# Sensor_tile2.net
KiCad netlist of a schematic drawn in EAGLE
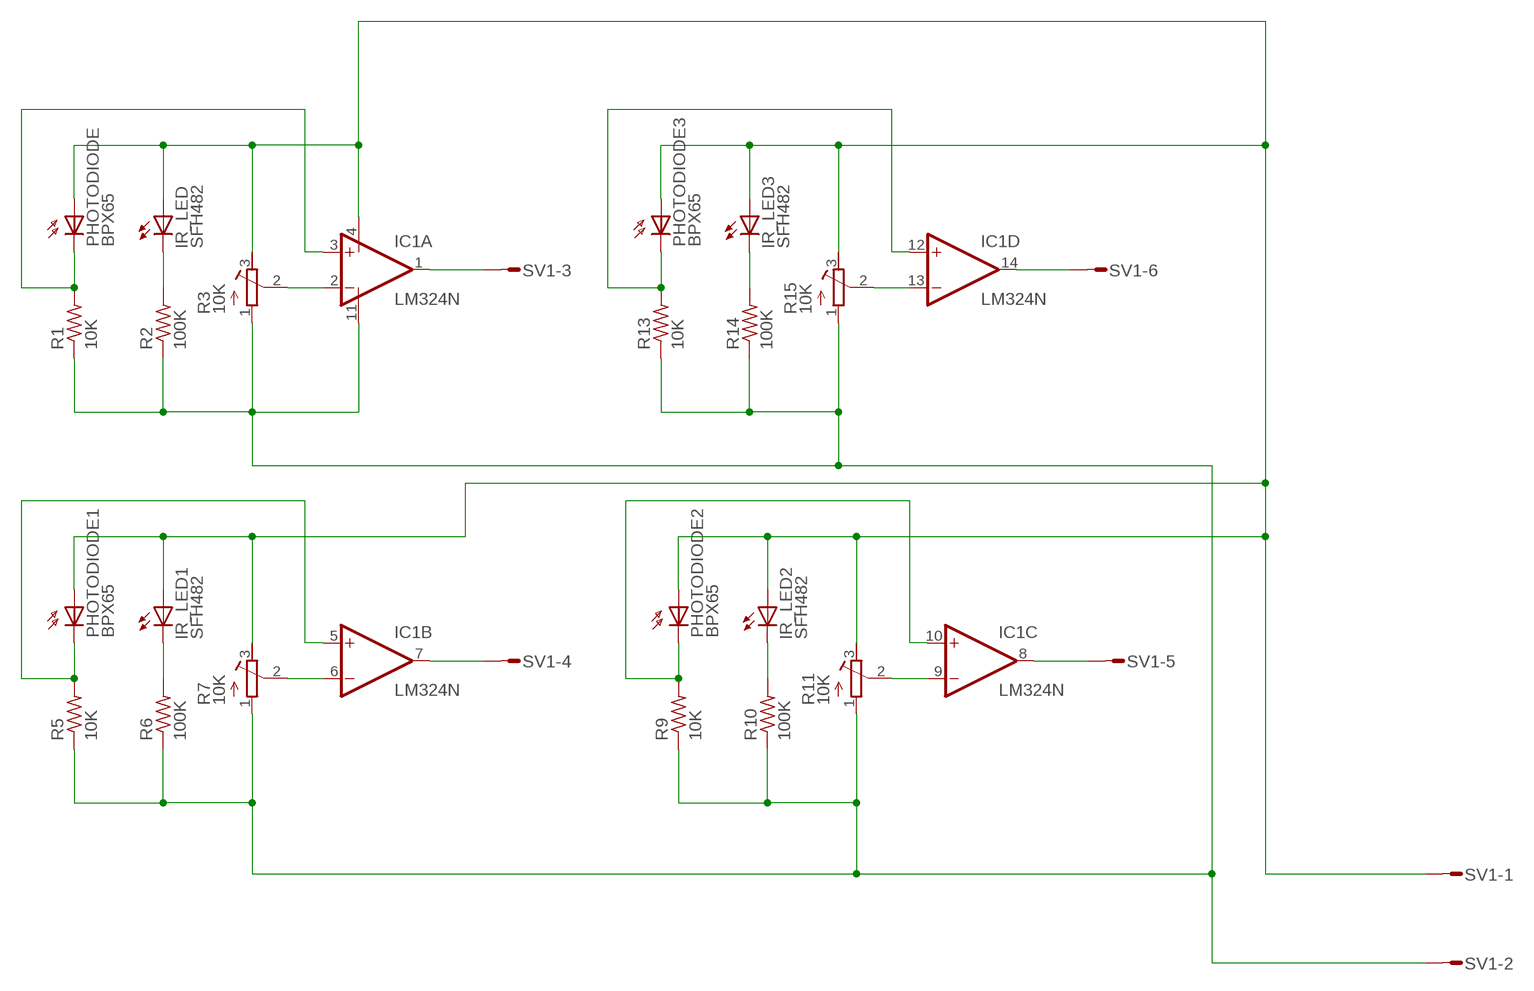
[diagram p0: schematic, sheet 1]

(export (version "E")
  (design (tool "Eeschema 10.0.6"))
  (components
    (comp (ref "IC1")
      (value "LM324N")
      (footprint "eagle-import:DIL14")
      (libsource (lib "eagle-import") (part "LM324N"))
    )
    (comp (ref "IR_LED")
      (value "SFH482")
      (footprint "eagle-import:SFH482")
      (libsource (lib "eagle-import") (part "SFH482"))
    )
    (comp (ref "IR_LED1")
      (value "SFH482")
      (footprint "eagle-import:SFH482")
      (libsource (lib "eagle-import") (part "SFH482"))
    )
    (comp (ref "IR_LED2")
      (value "SFH482")
      (footprint "eagle-import:SFH482")
      (libsource (lib "eagle-import") (part "SFH482"))
    )
    (comp (ref "IR_LED3")
      (value "SFH482")
      (footprint "eagle-import:SFH482")
      (libsource (lib "eagle-import") (part "SFH482"))
    )
    (comp (ref "PHOTODIODE")
      (value "BPX65")
      (footprint "eagle-import:BPX65")
      (fields (field (name "MPN") "BPX65."))
      (libsource (lib "eagle-import") (part "BPX65"))
    )
    (comp (ref "PHOTODIODE1")
      (value "BPX65")
      (footprint "eagle-import:BPX65")
      (fields (field (name "MPN") "BPX65."))
      (libsource (lib "eagle-import") (part "BPX65"))
    )
    (comp (ref "PHOTODIODE2")
      (value "BPX65")
      (footprint "eagle-import:BPX65")
      (fields (field (name "MPN") "BPX65."))
      (libsource (lib "eagle-import") (part "BPX65"))
    )
    (comp (ref "PHOTODIODE3")
      (value "BPX65")
      (footprint "eagle-import:BPX65")
      (fields (field (name "MPN") "BPX65."))
      (libsource (lib "eagle-import") (part "BPX65"))
    )
    (comp (ref "R1")
      (value "10K")
      (footprint "eagle-import:0204_7")
      (libsource (lib "eagle-import") (part "R-US_0204/7"))
    )
    (comp (ref "R2")
      (value "100K")
      (footprint "eagle-import:0204_7")
      (libsource (lib "eagle-import") (part "R-US_0204/7"))
    )
    (comp (ref "R3")
      (value "10K")
      (footprint "eagle-import:RTRIM4G_J")
      (libsource (lib "eagle-import") (part "R-TRIMM4G/J"))
    )
    (comp (ref "R5")
      (value "10K")
      (footprint "eagle-import:0204_7")
      (libsource (lib "eagle-import") (part "R-US_0204/7"))
    )
    (comp (ref "R6")
      (value "100K")
      (footprint "eagle-import:0204_7")
      (libsource (lib "eagle-import") (part "R-US_0204/7"))
    )
    (comp (ref "R7")
      (value "10K")
      (footprint "eagle-import:RTRIM4G_J")
      (libsource (lib "eagle-import") (part "R-TRIMM4G/J"))
    )
    (comp (ref "R9")
      (value "10K")
      (footprint "eagle-import:0204_7")
      (libsource (lib "eagle-import") (part "R-US_0204/7"))
    )
    (comp (ref "R10")
      (value "100K")
      (footprint "eagle-import:0204_7")
      (libsource (lib "eagle-import") (part "R-US_0204/7"))
    )
    (comp (ref "R11")
      (value "10K")
      (footprint "eagle-import:RTRIM4G_J")
      (libsource (lib "eagle-import") (part "R-TRIMM4G/J"))
    )
    (comp (ref "R13")
      (value "10K")
      (footprint "eagle-import:0204_7")
      (libsource (lib "eagle-import") (part "R-US_0204/7"))
    )
    (comp (ref "R14")
      (value "100K")
      (footprint "eagle-import:0204_7")
      (libsource (lib "eagle-import") (part "R-US_0204/7"))
    )
    (comp (ref "R15")
      (value "10K")
      (footprint "eagle-import:RTRIM4G_J")
      (libsource (lib "eagle-import") (part "R-TRIMM4G/J"))
    )
    (comp (ref "SV1")
      (value "L06P")
      (footprint "eagle-import:L06P")
      (libsource (lib "eagle-import") (part "L06P"))
    )
  )
  (nets
    (net (code "1") (name "Net-(IC1A-+IN)") (class "Default")
      (node (ref "IC1") (pin "3") (pinfunction "+IN_3") (pintype "input"))
      (node (ref "PHOTODIODE") (pin "K") (pinfunction "C_K") (pintype "passive"))
      (node (ref "R1") (pin "2") (pinfunction "2_2") (pintype "passive"))
    )
    (net (code "2") (name "Net-(IC1A--IN)") (class "Default")
      (node (ref "IC1") (pin "2") (pinfunction "-IN_2") (pintype "input"))
      (node (ref "R3") (pin "2") (pinfunction "S_2") (pintype "passive"))
    )
    (net (code "3") (name "Net-(IC1A-OUT)") (class "Default")
      (node (ref "IC1") (pin "1") (pinfunction "OUT_1") (pintype "output"))
      (node (ref "SV1") (pin "3") (pinfunction "S_3") (pintype "passive"))
    )
    (net (code "4") (name "Net-(IC1B-+IN)") (class "Default")
      (node (ref "IC1") (pin "5") (pinfunction "+IN_5") (pintype "input"))
      (node (ref "PHOTODIODE1") (pin "K") (pinfunction "C_K") (pintype "passive"))
      (node (ref "R5") (pin "2") (pinfunction "2_2") (pintype "passive"))
    )
    (net (code "5") (name "Net-(IC1B--IN)") (class "Default")
      (node (ref "IC1") (pin "6") (pinfunction "-IN_6") (pintype "input"))
      (node (ref "R7") (pin "2") (pinfunction "S_2") (pintype "passive"))
    )
    (net (code "6") (name "Net-(IC1B-OUT)") (class "Default")
      (node (ref "IC1") (pin "7") (pinfunction "OUT_7") (pintype "output"))
      (node (ref "SV1") (pin "4") (pinfunction "S_4") (pintype "passive"))
    )
    (net (code "7") (name "Net-(IC1C-+IN)") (class "Default")
      (node (ref "IC1") (pin "10") (pinfunction "+IN_10") (pintype "input"))
      (node (ref "PHOTODIODE2") (pin "K") (pinfunction "C_K") (pintype "passive"))
      (node (ref "R9") (pin "2") (pinfunction "2_2") (pintype "passive"))
    )
    (net (code "8") (name "Net-(IC1C--IN)") (class "Default")
      (node (ref "IC1") (pin "9") (pinfunction "-IN_9") (pintype "input"))
      (node (ref "R11") (pin "2") (pinfunction "S_2") (pintype "passive"))
    )
    (net (code "9") (name "Net-(IC1C-OUT)") (class "Default")
      (node (ref "IC1") (pin "8") (pinfunction "OUT_8") (pintype "output"))
      (node (ref "SV1") (pin "5") (pinfunction "S_5") (pintype "passive"))
    )
    (net (code "10") (name "Net-(IC1D-+IN)") (class "Default")
      (node (ref "IC1") (pin "12") (pinfunction "+IN_12") (pintype "input"))
      (node (ref "PHOTODIODE3") (pin "K") (pinfunction "C_K") (pintype "passive"))
      (node (ref "R13") (pin "2") (pinfunction "2_2") (pintype "passive"))
    )
    (net (code "11") (name "Net-(IC1D--IN)") (class "Default")
      (node (ref "IC1") (pin "13") (pinfunction "-IN_13") (pintype "input"))
      (node (ref "R15") (pin "2") (pinfunction "S_2") (pintype "passive"))
    )
    (net (code "12") (name "Net-(IC1D-OUT)") (class "Default")
      (node (ref "IC1") (pin "14") (pinfunction "OUT_14") (pintype "output"))
      (node (ref "SV1") (pin "6") (pinfunction "S_6") (pintype "passive"))
    )
    (net (code "13") (name "Net-(IC1E-V+)") (class "Default")
      (node (ref "IC1") (pin "4") (pinfunction "V+_4") (pintype "power_in"))
      (node (ref "IR_LED") (pin "A") (pinfunction "A_A") (pintype "passive"))
      (node (ref "IR_LED1") (pin "A") (pinfunction "A_A") (pintype "passive"))
      (node (ref "IR_LED2") (pin "A") (pinfunction "A_A") (pintype "passive"))
      (node (ref "IR_LED3") (pin "A") (pinfunction "A_A") (pintype "passive"))
      (node (ref "PHOTODIODE") (pin "A") (pinfunction "A_A") (pintype "passive"))
      (node (ref "PHOTODIODE1") (pin "A") (pinfunction "A_A") (pintype "passive"))
      (node (ref "PHOTODIODE2") (pin "A") (pinfunction "A_A") (pintype "passive"))
      (node (ref "PHOTODIODE3") (pin "A") (pinfunction "A_A") (pintype "passive"))
      (node (ref "R11") (pin "3") (pinfunction "E_3") (pintype "passive"))
      (node (ref "R15") (pin "3") (pinfunction "E_3") (pintype "passive"))
      (node (ref "R3") (pin "3") (pinfunction "E_3") (pintype "passive"))
      (node (ref "R7") (pin "3") (pinfunction "E_3") (pintype "passive"))
      (node (ref "SV1") (pin "1") (pinfunction "S_1") (pintype "passive"))
    )
    (net (code "14") (name "Net-(IC1E-V-)") (class "Default")
      (node (ref "IC1") (pin "11") (pinfunction "V-_11") (pintype "power_in"))
      (node (ref "R1") (pin "1") (pinfunction "1_1") (pintype "passive"))
      (node (ref "R10") (pin "1") (pinfunction "1_1") (pintype "passive"))
      (node (ref "R11") (pin "1") (pinfunction "A_1") (pintype "passive"))
      (node (ref "R13") (pin "1") (pinfunction "1_1") (pintype "passive"))
      (node (ref "R14") (pin "1") (pinfunction "1_1") (pintype "passive"))
      (node (ref "R15") (pin "1") (pinfunction "A_1") (pintype "passive"))
      (node (ref "R2") (pin "1") (pinfunction "1_1") (pintype "passive"))
      (node (ref "R3") (pin "1") (pinfunction "A_1") (pintype "passive"))
      (node (ref "R5") (pin "1") (pinfunction "1_1") (pintype "passive"))
      (node (ref "R6") (pin "1") (pinfunction "1_1") (pintype "passive"))
      (node (ref "R7") (pin "1") (pinfunction "A_1") (pintype "passive"))
      (node (ref "R9") (pin "1") (pinfunction "1_1") (pintype "passive"))
      (node (ref "SV1") (pin "2") (pinfunction "S_2") (pintype "passive"))
    )
    (net (code "15") (name "Net-(IR_LED-C)") (class "Default")
      (node (ref "IR_LED") (pin "K") (pinfunction "C_K") (pintype "passive"))
      (node (ref "R2") (pin "2") (pinfunction "2_2") (pintype "passive"))
    )
    (net (code "16") (name "Net-(IR_LED1-C)") (class "Default")
      (node (ref "IR_LED1") (pin "K") (pinfunction "C_K") (pintype "passive"))
      (node (ref "R6") (pin "2") (pinfunction "2_2") (pintype "passive"))
    )
    (net (code "17") (name "Net-(IR_LED2-C)") (class "Default")
      (node (ref "IR_LED2") (pin "K") (pinfunction "C_K") (pintype "passive"))
      (node (ref "R10") (pin "2") (pinfunction "2_2") (pintype "passive"))
    )
    (net (code "18") (name "Net-(IR_LED3-C)") (class "Default")
      (node (ref "IR_LED3") (pin "K") (pinfunction "C_K") (pintype "passive"))
      (node (ref "R14") (pin "2") (pinfunction "2_2") (pintype "passive"))
    )
  )
)
